# Power.net
KiCad netlist of a schematic drawn in Altium Designer
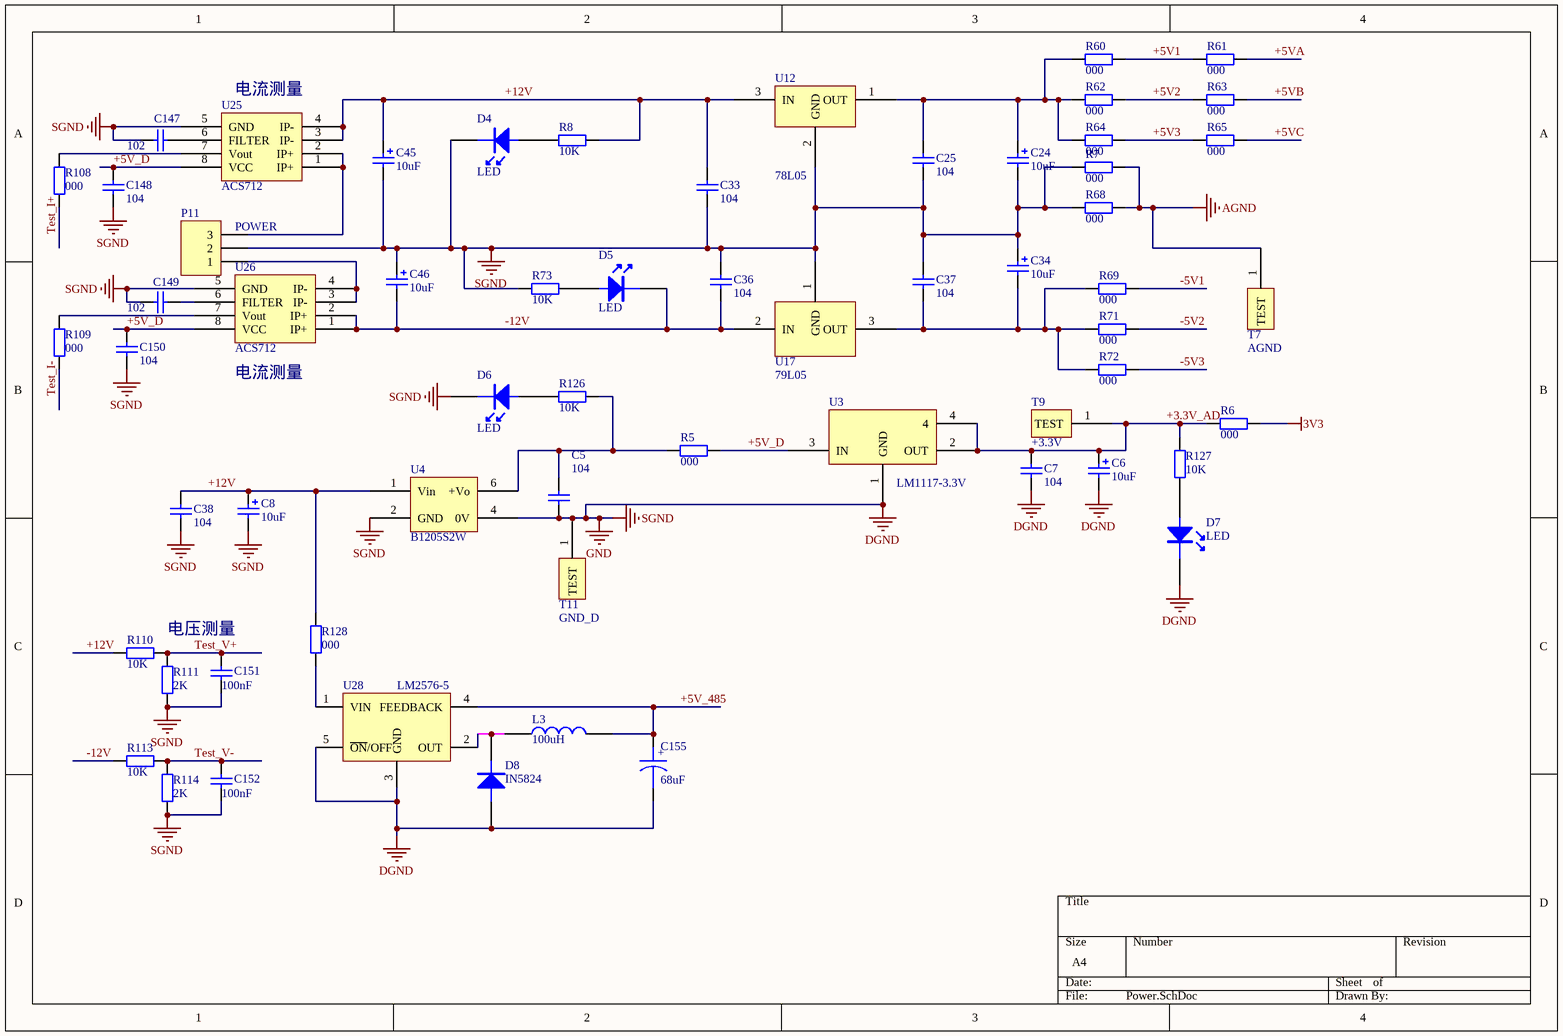
[diagram p0: Power.SchDoc]

(export (version "E")
  (design (tool "Eeschema 10.0.6"))
  (components
    (comp (ref "C5")
      (value "104")
      (footprint "0805C")
      (description "Capacitor")
      (fields (field (name "PUBLISHER") "Altium Limited"))
      (libsource (lib "Miscellaneous Devices") (part "Cap"))
    )
    (comp (ref "C6")
      (value "10uF")
      (footprint "C68uF")
      (description "Polarized Capacitor (Axial)")
      (fields (field (name "PUBLISHER") "Altium Limited"))
      (libsource (lib "Miscellaneous Devices") (part "Cap Pol2"))
    )
    (comp (ref "C7")
      (value "104")
      (footprint "0805C")
      (description "Capacitor")
      (fields (field (name "PUBLISHER") "Altium Limited"))
      (libsource (lib "Miscellaneous Devices") (part "Cap"))
    )
    (comp (ref "C8")
      (value "10uF")
      (footprint "C68uF")
      (description "Polarized Capacitor (Axial)")
      (fields (field (name "PUBLISHER") "Altium Limited"))
      (libsource (lib "Miscellaneous Devices") (part "Cap Pol2"))
    )
    (comp (ref "C24")
      (value "10uF")
      (footprint "C68uF")
      (description "Polarized Capacitor (Axial)")
      (fields (field (name "PUBLISHER") "Altium Limited"))
      (libsource (lib "Miscellaneous Devices") (part "Cap Pol2"))
    )
    (comp (ref "C25")
      (value "104")
      (footprint "0805C")
      (description "Capacitor")
      (fields (field (name "PUBLISHER") "Altium Limited"))
      (libsource (lib "Miscellaneous Devices") (part "Cap"))
    )
    (comp (ref "C33")
      (value "104")
      (footprint "0805C")
      (description "Capacitor")
      (fields (field (name "PUBLISHER") "Altium Limited"))
      (libsource (lib "Miscellaneous Devices") (part "Cap"))
    )
    (comp (ref "C34")
      (value "10uF")
      (footprint "C68uF")
      (description "Polarized Capacitor (Axial)")
      (fields (field (name "PUBLISHER") "Altium Limited"))
      (libsource (lib "Miscellaneous Devices") (part "Cap Pol2"))
    )
    (comp (ref "C36")
      (value "104")
      (footprint "0805C")
      (description "Capacitor")
      (fields (field (name "PUBLISHER") "Altium Limited"))
      (libsource (lib "Miscellaneous Devices") (part "Cap"))
    )
    (comp (ref "C37")
      (value "104")
      (footprint "0805C")
      (description "Capacitor")
      (fields (field (name "PUBLISHER") "Altium Limited"))
      (libsource (lib "Miscellaneous Devices") (part "Cap"))
    )
    (comp (ref "C38")
      (value "104")
      (footprint "0805C")
      (description "Capacitor")
      (fields (field (name "PUBLISHER") "Altium Limited"))
      (libsource (lib "Miscellaneous Devices") (part "Cap"))
    )
    (comp (ref "C45")
      (value "10uF")
      (footprint "C68uF")
      (description "Polarized Capacitor (Axial)")
      (fields (field (name "PUBLISHER") "Altium Limited"))
      (libsource (lib "Miscellaneous Devices") (part "Cap Pol2"))
    )
    (comp (ref "C46")
      (value "10uF")
      (footprint "C68uF")
      (description "Polarized Capacitor (Axial)")
      (fields (field (name "PUBLISHER") "Altium Limited"))
      (libsource (lib "Miscellaneous Devices") (part "Cap Pol2"))
    )
    (comp (ref "C147")
      (value "102")
      (footprint "0603")
      (description "Capacitor")
      (fields (field (name "PUBLISHER") "Altium Limited"))
      (libsource (lib "Miscellaneous Devices") (part "Cap"))
    )
    (comp (ref "C148")
      (value "104")
      (footprint "0603")
      (description "Capacitor")
      (fields (field (name "PUBLISHER") "Altium Limited"))
      (libsource (lib "Miscellaneous Devices") (part "Cap"))
    )
    (comp (ref "C149")
      (value "102")
      (footprint "0603")
      (description "Capacitor")
      (fields (field (name "PUBLISHER") "Altium Limited"))
      (libsource (lib "Miscellaneous Devices") (part "Cap"))
    )
    (comp (ref "C150")
      (value "104")
      (footprint "0603")
      (description "Capacitor")
      (fields (field (name "PUBLISHER") "Altium Limited"))
      (libsource (lib "Miscellaneous Devices") (part "Cap"))
    )
    (comp (ref "C151")
      (value "100nF")
      (footprint "0603")
      (description "Capacitor")
      (fields (field (name "Comment") "Cap") (field (name "PUBLISHER") "Altium Limited"))
      (libsource (lib "Miscellaneous Devices") (part "Cap"))
    )
    (comp (ref "C152")
      (value "100nF")
      (footprint "0603")
      (description "Capacitor")
      (fields (field (name "Comment") "Cap") (field (name "PUBLISHER") "Altium Limited"))
      (libsource (lib "Miscellaneous Devices") (part "Cap"))
    )
    (comp (ref "C155")
      (value "68uF")
      (footprint "C68uF")
      (description "Capacitor")
      (libsource (lib "*") (part "CAPACITOR POL"))
    )
    (comp (ref "D4") (value "LED") (footprint "0805_LED") (libsource (lib "*") (part "LED")))
    (comp (ref "D5") (value "LED") (footprint "0805_LED") (libsource (lib "*") (part "LED")))
    (comp (ref "D6") (value "LED") (footprint "0805_LED") (libsource (lib "*") (part "LED")))
    (comp (ref "D7") (value "LED") (footprint "0805_LED") (libsource (lib "*") (part "LED")))
    (comp (ref "D8")
      (value "IN5824")
      (footprint "1N5824")
      (description "Diode")
      (libsource (lib "*") (part "DIODE"))
    )
    (comp (ref "L3") (value "100uH") (footprint "L100uH") (libsource (lib "*") (part "INDUCTOR")))
    (comp (ref "P11")
      (value "POWER")
      (footprint "SIP3-5.08mm")
      (description "Header, 3-Pin")
      (fields (field (name "PUBLISHER") "Altium Limited"))
      (libsource (lib "Miscellaneous Connectors") (part "Header 3"))
    )
    (comp (ref "R5")
      (value "000")
      (footprint "0805R")
      (description "Resistor")
      (fields (field (name "PUBLISHER") "Altium Limited"))
      (libsource (lib "Miscellaneous Devices") (part "Res2"))
    )
    (comp (ref "R6")
      (value "000")
      (footprint "0805R")
      (description "Resistor")
      (fields (field (name "PUBLISHER") "Altium Limited"))
      (libsource (lib "Miscellaneous Devices") (part "Res2"))
    )
    (comp (ref "R7")
      (value "000")
      (footprint "I_ON")
      (description "Resistor")
      (fields (field (name "PUBLISHER") "Altium Limited"))
      (libsource (lib "Miscellaneous Devices") (part "Res2"))
    )
    (comp (ref "R8")
      (value "10K")
      (footprint "0603")
      (description "Resistor")
      (fields (field (name "Comment") "Res2") (field (name "PUBLISHER") "Altium Limited"))
      (libsource (lib "") (part "Res2_3"))
    )
    (comp (ref "R60")
      (value "000")
      (footprint "0805R")
      (description "Resistor")
      (fields (field (name "PUBLISHER") "Altium Limited"))
      (libsource (lib "Miscellaneous Devices") (part "Res2"))
    )
    (comp (ref "R61")
      (value "000")
      (footprint "0805R")
      (description "Resistor")
      (fields (field (name "PUBLISHER") "Altium Limited"))
      (libsource (lib "Miscellaneous Devices") (part "Res2"))
    )
    (comp (ref "R62")
      (value "000")
      (footprint "0805R")
      (description "Resistor")
      (fields (field (name "PUBLISHER") "Altium Limited"))
      (libsource (lib "Miscellaneous Devices") (part "Res2"))
    )
    (comp (ref "R63")
      (value "000")
      (footprint "0805R")
      (description "Resistor")
      (fields (field (name "PUBLISHER") "Altium Limited"))
      (libsource (lib "Miscellaneous Devices") (part "Res2"))
    )
    (comp (ref "R64")
      (value "000")
      (footprint "0805R")
      (description "Resistor")
      (fields (field (name "PUBLISHER") "Altium Limited"))
      (libsource (lib "Miscellaneous Devices") (part "Res2"))
    )
    (comp (ref "R65")
      (value "000")
      (footprint "0805R")
      (description "Resistor")
      (fields (field (name "PUBLISHER") "Altium Limited"))
      (libsource (lib "Miscellaneous Devices") (part "Res2"))
    )
    (comp (ref "R68")
      (value "000")
      (footprint "I_ON")
      (description "Resistor")
      (fields (field (name "PUBLISHER") "Altium Limited"))
      (libsource (lib "Miscellaneous Devices") (part "Res2"))
    )
    (comp (ref "R69")
      (value "000")
      (footprint "0805R")
      (description "Resistor")
      (fields (field (name "PUBLISHER") "Altium Limited"))
      (libsource (lib "Miscellaneous Devices") (part "Res2"))
    )
    (comp (ref "R71")
      (value "000")
      (footprint "0805R")
      (description "Resistor")
      (fields (field (name "PUBLISHER") "Altium Limited"))
      (libsource (lib "Miscellaneous Devices") (part "Res2"))
    )
    (comp (ref "R72")
      (value "000")
      (footprint "0805R")
      (description "Resistor")
      (fields (field (name "PUBLISHER") "Altium Limited"))
      (libsource (lib "Miscellaneous Devices") (part "Res2"))
    )
    (comp (ref "R73")
      (value "10K")
      (footprint "0603")
      (description "Resistor")
      (fields (field (name "Comment") "Res2") (field (name "PUBLISHER") "Altium Limited"))
      (libsource (lib "Miscellaneous Devices") (part "Res2"))
    )
    (comp (ref "R108")
      (value "000")
      (footprint "0603")
      (description "Resistor")
      (fields (field (name "PUBLISHER") "Altium Limited"))
      (libsource (lib "") (part "Res2_2"))
    )
    (comp (ref "R109")
      (value "000")
      (footprint "0603")
      (description "Resistor")
      (fields (field (name "PUBLISHER") "Altium Limited"))
      (libsource (lib "") (part "Res2_2"))
    )
    (comp (ref "R110")
      (value "10K")
      (footprint "0603")
      (description "Resistor")
      (fields (field (name "Comment") "Res2") (field (name "PUBLISHER") "Altium Limited"))
      (libsource (lib "Miscellaneous Devices") (part "Res2"))
    )
    (comp (ref "R111")
      (value "2K")
      (footprint "0603")
      (description "Resistor")
      (fields (field (name "Comment") "Res2") (field (name "PUBLISHER") "Altium Limited"))
      (libsource (lib "") (part "Res2_1"))
    )
    (comp (ref "R113")
      (value "10K")
      (footprint "0603")
      (description "Resistor")
      (fields (field (name "Comment") "Res2") (field (name "PUBLISHER") "Altium Limited"))
      (libsource (lib "Miscellaneous Devices") (part "Res2"))
    )
    (comp (ref "R114")
      (value "2K")
      (footprint "0603")
      (description "Resistor")
      (fields (field (name "Comment") "Res2") (field (name "PUBLISHER") "Altium Limited"))
      (libsource (lib "") (part "Res2_1"))
    )
    (comp (ref "R126")
      (value "10K")
      (footprint "0603")
      (description "Resistor")
      (fields (field (name "Comment") "Res2") (field (name "PUBLISHER") "Altium Limited"))
      (libsource (lib "") (part "Res2_3"))
    )
    (comp (ref "R127")
      (value "10K")
      (footprint "0603")
      (description "Resistor")
      (fields (field (name "Comment") "Res2") (field (name "PUBLISHER") "Altium Limited"))
      (libsource (lib "") (part "Res2_2"))
    )
    (comp (ref "R128")
      (value "000")
      (footprint "0805R")
      (description "Resistor")
      (fields (field (name "PUBLISHER") "Altium Limited"))
      (libsource (lib "") (part "Res2_1"))
    )
    (comp (ref "T7") (value "AGND") (footprint "TEST") (libsource (lib "") (part "TEST_1")))
    (comp (ref "T9") (value "+3.3V") (footprint "TEST") (libsource (lib "Schlib1") (part "TEST")))
    (comp (ref "T11") (value "GND_D") (footprint "TEST") (libsource (lib "") (part "TEST_1")))
    (comp (ref "U3")
      (value "LM1117-3.3V")
      (footprint "SOT223")
      (libsource (lib "Schlib1") (part "LM1117-3.3V"))
    )
    (comp (ref "U4") (value "B1205S2W") (footprint "B1205SW") (libsource (lib "Schlib1") (part "B1205S2W")))
    (comp (ref "U12") (value "78L05") (footprint "SOT89-M") (libsource (lib "Schlib1") (part "78L05")))
    (comp (ref "U17") (value "79L05") (libsource (lib "Schlib1") (part "79L05")))
    (comp (ref "U25") (value "ACS712") (footprint "SO8") (libsource (lib "Schlib1") (part "ACS712")))
    (comp (ref "U26") (value "ACS712") (footprint "SO8") (libsource (lib "Schlib1") (part "ACS712")))
    (comp (ref "U28") (value "LM2576-5") (footprint "lm2596") (libsource (lib "*") (part "LM2596-5")))
  )
  (nets
    (net (code "1") (name "/+3.3V_AD") (class "Default")
      (node (ref "C6") (pin "1") (pinfunction "1_1") (pintype "passive"))
      (node (ref "C7") (pin "1") (pinfunction "1_1") (pintype "passive"))
      (node (ref "R127") (pin "2") (pinfunction "2_2") (pintype "passive"))
      (node (ref "R6") (pin "2") (pinfunction "2_2") (pintype "passive"))
      (node (ref "T9") (pin "1") (pinfunction "TEST_1") (pintype "passive"))
      (node (ref "U3") (pin "2") (pinfunction "OUT_2") (pintype "passive"))
      (node (ref "U3") (pin "4") (pinfunction "4_4") (pintype "passive"))
    )
    (net (code "2") (name "/+5V1") (class "Default")
      (node (ref "R60") (pin "1") (pinfunction "1_1") (pintype "passive"))
      (node (ref "R61") (pin "2") (pinfunction "2_2") (pintype "passive"))
    )
    (net (code "3") (name "/+5V2") (class "Default")
      (node (ref "R62") (pin "1") (pinfunction "1_1") (pintype "passive"))
      (node (ref "R63") (pin "2") (pinfunction "2_2") (pintype "passive"))
    )
    (net (code "4") (name "/+5V3") (class "Default")
      (node (ref "R64") (pin "1") (pinfunction "1_1") (pintype "passive"))
      (node (ref "R65") (pin "2") (pinfunction "2_2") (pintype "passive"))
    )
    (net (code "5") (name "/+5VA") (class "Default")
      (node (ref "R61") (pin "1") (pinfunction "1_1") (pintype "passive"))
    )
    (net (code "6") (name "/+5VB") (class "Default")
      (node (ref "R63") (pin "1") (pinfunction "1_1") (pintype "passive"))
    )
    (net (code "7") (name "/+5VC") (class "Default")
      (node (ref "R65") (pin "1") (pinfunction "1_1") (pintype "passive"))
    )
    (net (code "8") (name "/+5V_485") (class "Default")
      (node (ref "C155") (pin "1") (pinfunction "1_1") (pintype "passive"))
      (node (ref "L3") (pin "2") (pinfunction "2_2") (pintype "passive"))
      (node (ref "U28") (pin "4") (pinfunction "FEEDBACK_4") (pintype "passive"))
    )
    (net (code "9") (name "/+5V_D") (class "Default")
      (node (ref "C148") (pin "1") (pinfunction "1_1") (pintype "passive"))
      (node (ref "C150") (pin "1") (pinfunction "1_1") (pintype "passive"))
      (node (ref "R5") (pin "1") (pinfunction "1_1") (pintype "passive"))
      (node (ref "U25") (pin "8") (pinfunction "VCC_8") (pintype "passive"))
      (node (ref "U26") (pin "8") (pinfunction "VCC_8") (pintype "passive"))
      (node (ref "U3") (pin "3") (pinfunction "IN_3") (pintype "passive"))
    )
    (net (code "10") (name "/+12V") (class "Default")
      (node (ref "C33") (pin "1") (pinfunction "1_1") (pintype "passive"))
      (node (ref "C38") (pin "1") (pinfunction "1_1") (pintype "passive"))
      (node (ref "C45") (pin "1") (pinfunction "1_1") (pintype "passive"))
      (node (ref "C8") (pin "1") (pinfunction "1_1") (pintype "passive"))
      (node (ref "R110") (pin "2") (pinfunction "2_2") (pintype "passive"))
      (node (ref "R128") (pin "1") (pinfunction "1_1") (pintype "passive"))
      (node (ref "R8") (pin "2") (pinfunction "2_2") (pintype "passive"))
      (node (ref "U12") (pin "3") (pinfunction "IN_3") (pintype "passive"))
      (node (ref "U25") (pin "3") (pinfunction "IP-_3") (pintype "passive"))
      (node (ref "U25") (pin "4") (pinfunction "IP-_4") (pintype "passive"))
      (node (ref "U4") (pin "1") (pinfunction "Vin_1") (pintype "passive"))
    )
    (net (code "11") (name "/-5V1") (class "Default")
      (node (ref "R69") (pin "1") (pinfunction "1_1") (pintype "passive"))
    )
    (net (code "12") (name "/-5V2") (class "Default")
      (node (ref "R71") (pin "1") (pinfunction "1_1") (pintype "passive"))
    )
    (net (code "13") (name "/-5V3") (class "Default")
      (node (ref "R72") (pin "1") (pinfunction "1_1") (pintype "passive"))
    )
    (net (code "14") (name "/-12V") (class "Default")
      (node (ref "C36") (pin "2") (pinfunction "2_2") (pintype "passive"))
      (node (ref "C46") (pin "2") (pinfunction "2_2") (pintype "passive"))
      (node (ref "D5") (pin "2") (pinfunction "K_2") (pintype "passive"))
      (node (ref "R113") (pin "2") (pinfunction "2_2") (pintype "passive"))
      (node (ref "U17") (pin "2") (pinfunction "IN_2") (pintype "passive"))
      (node (ref "U26") (pin "1") (pinfunction "IP+_1") (pintype "passive"))
      (node (ref "U26") (pin "2") (pinfunction "IP+_2") (pintype "passive"))
    )
    (net (code "15") (name "/Test_I+") (class "Default")
      (node (ref "R108") (pin "1") (pinfunction "1_1") (pintype "passive"))
    )
    (net (code "16") (name "/Test_I-") (class "Default")
      (node (ref "R109") (pin "1") (pinfunction "1_1") (pintype "passive"))
    )
    (net (code "17") (name "/Test_V+") (class "Default")
      (node (ref "C151") (pin "2") (pinfunction "2_2") (pintype "passive"))
      (node (ref "R110") (pin "1") (pinfunction "1_1") (pintype "passive"))
      (node (ref "R111") (pin "1") (pinfunction "1_1") (pintype "passive"))
    )
    (net (code "18") (name "/Test_V-") (class "Default")
      (node (ref "C152") (pin "2") (pinfunction "2_2") (pintype "passive"))
      (node (ref "R113") (pin "1") (pinfunction "1_1") (pintype "passive"))
      (node (ref "R114") (pin "1") (pinfunction "1_1") (pintype "passive"))
    )
    (net (code "19") (name "3V3") (class "Default")
      (node (ref "R6") (pin "1") (pinfunction "1_1") (pintype "passive"))
    )
    (net (code "20") (name "AGND") (class "Default")
      (node (ref "R68") (pin "1") (pinfunction "1_1") (pintype "passive"))
      (node (ref "R7") (pin "1") (pinfunction "1_1") (pintype "passive"))
      (node (ref "T7") (pin "1") (pinfunction "TEST_1") (pintype "passive"))
    )
    (net (code "21") (name "DGND") (class "Default")
      (node (ref "C147") (pin "1") (pinfunction "1_1") (pintype "passive"))
      (node (ref "C148") (pin "2") (pinfunction "2_2") (pintype "passive"))
      (node (ref "C149") (pin "1") (pinfunction "1_1") (pintype "passive"))
      (node (ref "C150") (pin "2") (pinfunction "2_2") (pintype "passive"))
      (node (ref "C151") (pin "1") (pinfunction "1_1") (pintype "passive"))
      (node (ref "C152") (pin "1") (pinfunction "1_1") (pintype "passive"))
      (node (ref "C155") (pin "2") (pinfunction "2_2") (pintype "passive"))
      (node (ref "C24") (pin "2") (pinfunction "2_2") (pintype "passive"))
      (node (ref "C25") (pin "2") (pinfunction "2_2") (pintype "passive"))
      (node (ref "C33") (pin "2") (pinfunction "2_2") (pintype "passive"))
      (node (ref "C34") (pin "1") (pinfunction "1_1") (pintype "passive"))
      (node (ref "C36") (pin "1") (pinfunction "1_1") (pintype "passive"))
      (node (ref "C37") (pin "1") (pinfunction "1_1") (pintype "passive"))
      (node (ref "C38") (pin "2") (pinfunction "2_2") (pintype "passive"))
      (node (ref "C45") (pin "2") (pinfunction "2_2") (pintype "passive"))
      (node (ref "C46") (pin "1") (pinfunction "1_1") (pintype "passive"))
      (node (ref "C5") (pin "2") (pinfunction "2_2") (pintype "passive"))
      (node (ref "C6") (pin "2") (pinfunction "2_2") (pintype "passive"))
      (node (ref "C7") (pin "2") (pinfunction "2_2") (pintype "passive"))
      (node (ref "C8") (pin "2") (pinfunction "2_2") (pintype "passive"))
      (node (ref "D4") (pin "2") (pinfunction "K_2") (pintype "passive"))
      (node (ref "D6") (pin "2") (pinfunction "K_2") (pintype "passive"))
      (node (ref "D7") (pin "2") (pinfunction "K_2") (pintype "passive"))
      (node (ref "D8") (pin "1") (pinfunction "A_1") (pintype "passive"))
      (node (ref "P11") (pin "2") (pinfunction "2_2") (pintype "passive"))
      (node (ref "R111") (pin "2") (pinfunction "2_2") (pintype "passive"))
      (node (ref "R114") (pin "2") (pinfunction "2_2") (pintype "passive"))
      (node (ref "R68") (pin "2") (pinfunction "2_2") (pintype "passive"))
      (node (ref "R7") (pin "2") (pinfunction "2_2") (pintype "passive"))
      (node (ref "R73") (pin "2") (pinfunction "2_2") (pintype "passive"))
      (node (ref "T11") (pin "1") (pinfunction "TEST_1") (pintype "passive"))
      (node (ref "U12") (pin "2") (pinfunction "GND_2") (pintype "passive"))
      (node (ref "U17") (pin "1") (pinfunction "GND_1") (pintype "passive"))
      (node (ref "U25") (pin "5") (pinfunction "GND_5") (pintype "passive"))
      (node (ref "U26") (pin "5") (pinfunction "GND_5") (pintype "passive"))
      (node (ref "U28") (pin "3") (pinfunction "GND_3") (pintype "passive"))
      (node (ref "U28") (pin "5") (pinfunction "~{ON}/OFF_5") (pintype "passive"))
      (node (ref "U3") (pin "1") (pinfunction "GND_1") (pintype "passive"))
      (node (ref "U4") (pin "2") (pinfunction "GND_2") (pintype "passive"))
      (node (ref "U4") (pin "4") (pinfunction "0V_4") (pintype "passive"))
    )
    (net (code "22") (name "Net-(D4-A)") (class "Default")
      (node (ref "D4") (pin "1") (pinfunction "A_1") (pintype "passive"))
      (node (ref "R8") (pin "1") (pinfunction "1_1") (pintype "passive"))
    )
    (net (code "23") (name "Net-(D5-A)") (class "Default")
      (node (ref "D5") (pin "1") (pinfunction "A_1") (pintype "passive"))
      (node (ref "R73") (pin "1") (pinfunction "1_1") (pintype "passive"))
    )
    (net (code "24") (name "Net-(D6-A)") (class "Default")
      (node (ref "D6") (pin "1") (pinfunction "A_1") (pintype "passive"))
      (node (ref "R126") (pin "1") (pinfunction "1_1") (pintype "passive"))
    )
    (net (code "25") (name "Net-(D7-A)") (class "Default")
      (node (ref "D7") (pin "1") (pinfunction "A_1") (pintype "passive"))
      (node (ref "R127") (pin "1") (pinfunction "1_1") (pintype "passive"))
    )
    (net (code "26") (name "Net-(D8-K)") (class "Default")
      (node (ref "D8") (pin "2") (pinfunction "K_2") (pintype "passive"))
      (node (ref "L3") (pin "1") (pinfunction "1_1") (pintype "passive"))
      (node (ref "U28") (pin "2") (pinfunction "OUT_2") (pintype "passive"))
    )
    (net (code "27") (name "Net-(P11-Pad1)") (class "Default")
      (node (ref "P11") (pin "1") (pinfunction "1_1") (pintype "passive"))
      (node (ref "U26") (pin "3") (pinfunction "IP-_3") (pintype "passive"))
      (node (ref "U26") (pin "4") (pinfunction "IP-_4") (pintype "passive"))
    )
    (net (code "28") (name "Net-(P11-Pad3)") (class "Default")
      (node (ref "P11") (pin "3") (pinfunction "3_3") (pintype "passive"))
      (node (ref "U25") (pin "1") (pinfunction "IP+_1") (pintype "passive"))
      (node (ref "U25") (pin "2") (pinfunction "IP+_2") (pintype "passive"))
    )
    (net (code "29") (name "Net-(U4-+Vo)") (class "Default")
      (node (ref "C5") (pin "1") (pinfunction "1_1") (pintype "passive"))
      (node (ref "R126") (pin "2") (pinfunction "2_2") (pintype "passive"))
      (node (ref "R5") (pin "2") (pinfunction "2_2") (pintype "passive"))
      (node (ref "U4") (pin "6") (pinfunction "+Vo_6") (pintype "passive"))
    )
    (net (code "30") (name "Net-(U12-OUT)") (class "Default")
      (node (ref "C24") (pin "1") (pinfunction "1_1") (pintype "passive"))
      (node (ref "C25") (pin "1") (pinfunction "1_1") (pintype "passive"))
      (node (ref "R60") (pin "2") (pinfunction "2_2") (pintype "passive"))
      (node (ref "R62") (pin "2") (pinfunction "2_2") (pintype "passive"))
      (node (ref "R64") (pin "2") (pinfunction "2_2") (pintype "passive"))
      (node (ref "U12") (pin "1") (pinfunction "OUT_1") (pintype "passive"))
    )
    (net (code "31") (name "Net-(U17-OUT)") (class "Default")
      (node (ref "C34") (pin "2") (pinfunction "2_2") (pintype "passive"))
      (node (ref "C37") (pin "2") (pinfunction "2_2") (pintype "passive"))
      (node (ref "R69") (pin "2") (pinfunction "2_2") (pintype "passive"))
      (node (ref "R71") (pin "2") (pinfunction "2_2") (pintype "passive"))
      (node (ref "R72") (pin "2") (pinfunction "2_2") (pintype "passive"))
      (node (ref "U17") (pin "3") (pinfunction "OUT_3") (pintype "passive"))
    )
    (net (code "32") (name "Net-(U25-FILTER)") (class "Default")
      (node (ref "C147") (pin "2") (pinfunction "2_2") (pintype "passive"))
      (node (ref "U25") (pin "6") (pinfunction "FILTER_6") (pintype "passive"))
    )
    (net (code "33") (name "Net-(U25-Vout)") (class "Default")
      (node (ref "R108") (pin "2") (pinfunction "2_2") (pintype "passive"))
      (node (ref "U25") (pin "7") (pinfunction "Vout_7") (pintype "passive"))
    )
    (net (code "34") (name "Net-(U26-FILTER)") (class "Default")
      (node (ref "C149") (pin "2") (pinfunction "2_2") (pintype "passive"))
      (node (ref "U26") (pin "6") (pinfunction "FILTER_6") (pintype "passive"))
    )
    (net (code "35") (name "Net-(U26-Vout)") (class "Default")
      (node (ref "R109") (pin "2") (pinfunction "2_2") (pintype "passive"))
      (node (ref "U26") (pin "7") (pinfunction "Vout_7") (pintype "passive"))
    )
    (net (code "36") (name "Net-(U28-VIN)") (class "Default")
      (node (ref "R128") (pin "2") (pinfunction "2_2") (pintype "passive"))
      (node (ref "U28") (pin "1") (pinfunction "VIN_1") (pintype "passive"))
    )
  )
)
